# Schematics_Rev_2.net
KiCad netlist of a schematic drawn in EAGLE
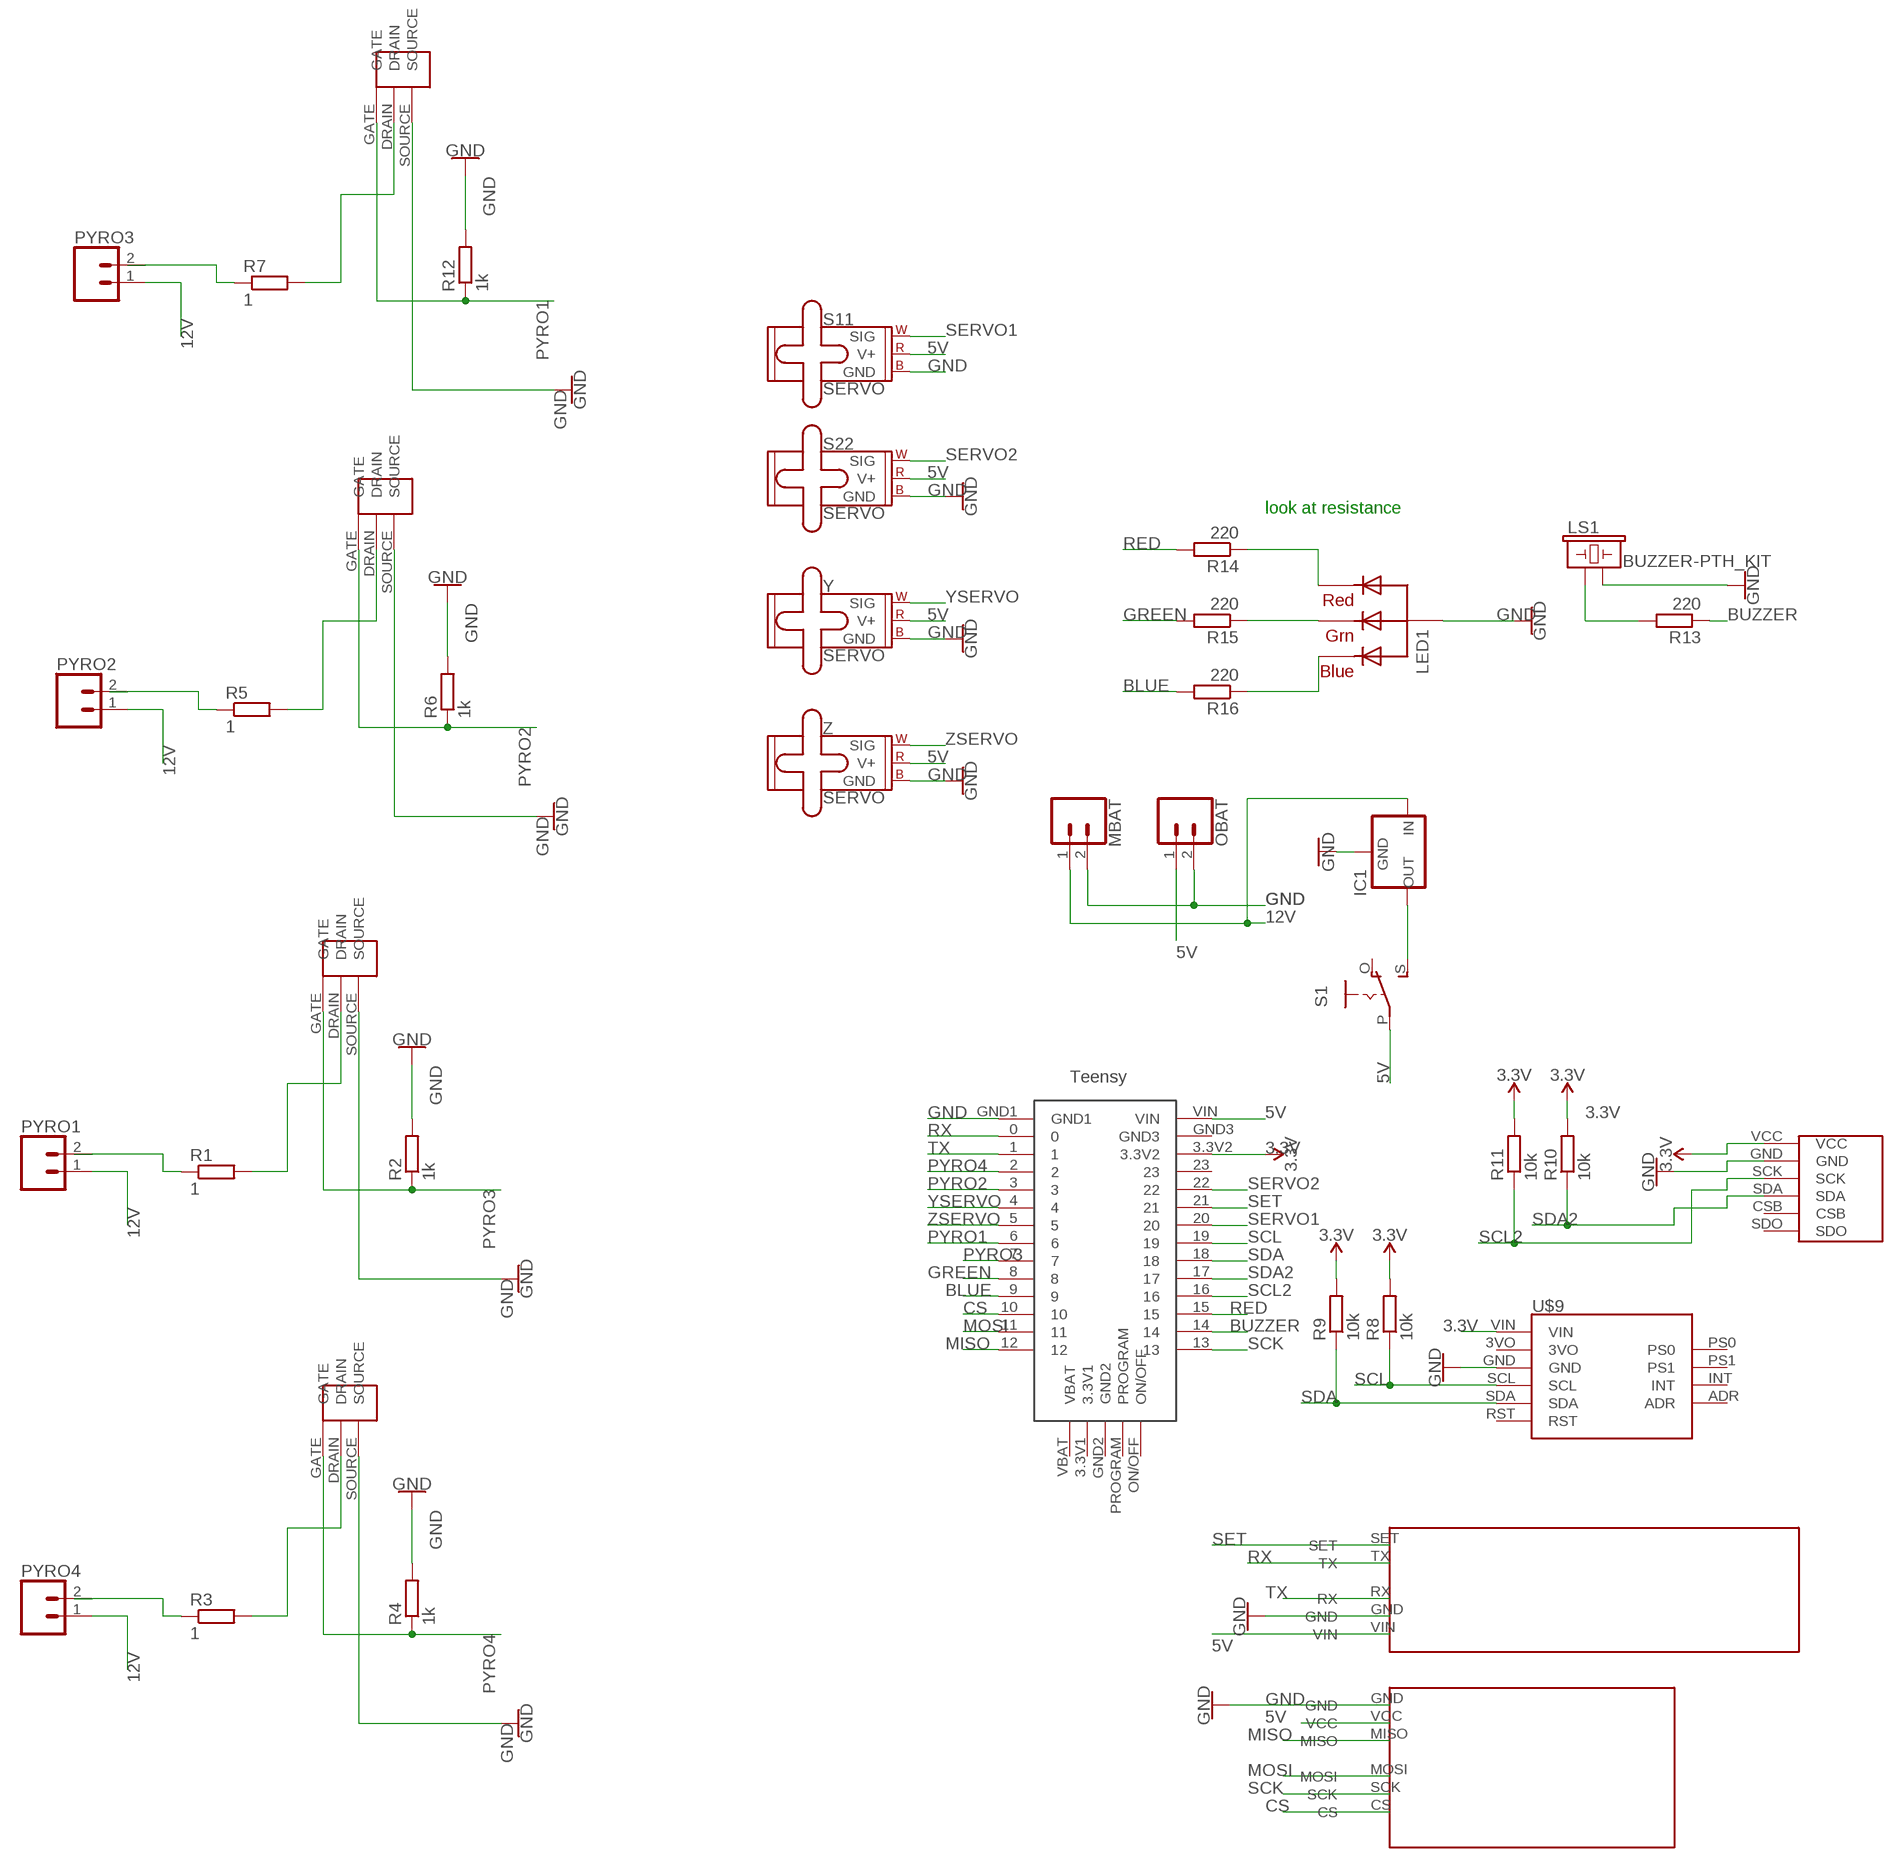
[diagram p0: schematic, sheet 1]

(export (version "E")
  (design (tool "Eeschema 10.0.6"))
  (components
    (comp (ref "IC1")
      (value "78XXS")
      (footprint "eagle-import:78XXS")
      (libsource (lib "eagle-import") (part "78XXS"))
    )
    (comp (ref "LED1")
      (value "RGBLED_CA-5MM")
      (footprint "eagle-import:LED5MMRGB")
      (libsource (lib "eagle-import") (part "RGBLED_CA-5MM"))
    )
    (comp (ref "LS1")
      (value "BUZZER-PTH_KIT")
      (footprint "eagle-import:BUZZER-12MM-KIT")
      (libsource (lib "eagle-import") (part "BUZZER-PTH_KIT"))
    )
    (comp (ref "MBAT")
      (value "CONN_023.5MM")
      (footprint "eagle-import:SCREWTERMINAL-3.5MM-2")
      (libsource (lib "eagle-import") (part "CONN_023.5MM"))
    )
    (comp (ref "OBAT")
      (value "CONN_023.5MM")
      (footprint "eagle-import:SCREWTERMINAL-3.5MM-2")
      (libsource (lib "eagle-import") (part "CONN_023.5MM"))
    )
    (comp (ref "PYRO1")
      (value "CONN_023.5MM")
      (footprint "eagle-import:SCREWTERMINAL-3.5MM-2")
      (libsource (lib "eagle-import") (part "CONN_023.5MM"))
    )
    (comp (ref "PYRO2")
      (value "CONN_023.5MM")
      (footprint "eagle-import:SCREWTERMINAL-3.5MM-2")
      (libsource (lib "eagle-import") (part "CONN_023.5MM"))
    )
    (comp (ref "PYRO3")
      (value "CONN_023.5MM")
      (footprint "eagle-import:SCREWTERMINAL-3.5MM-2")
      (libsource (lib "eagle-import") (part "CONN_023.5MM"))
    )
    (comp (ref "PYRO4")
      (value "CONN_023.5MM")
      (footprint "eagle-import:SCREWTERMINAL-3.5MM-2")
      (libsource (lib "eagle-import") (part "CONN_023.5MM"))
    )
    (comp (ref "R1")
      (value "1")
      (footprint "eagle-import:0204_7")
      (libsource (lib "eagle-import") (part "R-EU_0204/7"))
    )
    (comp (ref "R2")
      (value "1k")
      (footprint "eagle-import:0204_7")
      (libsource (lib "eagle-import") (part "R-EU_0204/7"))
    )
    (comp (ref "R3")
      (value "1")
      (footprint "eagle-import:0204_7")
      (libsource (lib "eagle-import") (part "R-EU_0204/7"))
    )
    (comp (ref "R4")
      (value "1k")
      (footprint "eagle-import:0204_7")
      (libsource (lib "eagle-import") (part "R-EU_0204/7"))
    )
    (comp (ref "R5")
      (value "1")
      (footprint "eagle-import:0204_7")
      (libsource (lib "eagle-import") (part "R-EU_0204/7"))
    )
    (comp (ref "R6")
      (value "1k")
      (footprint "eagle-import:0204_7")
      (libsource (lib "eagle-import") (part "R-EU_0204/7"))
    )
    (comp (ref "R7")
      (value "1")
      (footprint "eagle-import:0204_7")
      (libsource (lib "eagle-import") (part "R-EU_0204/7"))
    )
    (comp (ref "R8")
      (value "10k")
      (footprint "eagle-import:0204_7")
      (libsource (lib "eagle-import") (part "R-EU_0204/7"))
    )
    (comp (ref "R9")
      (value "10k")
      (footprint "eagle-import:0204_7")
      (libsource (lib "eagle-import") (part "R-EU_0204/7"))
    )
    (comp (ref "R10")
      (value "10k")
      (footprint "eagle-import:0204_7")
      (libsource (lib "eagle-import") (part "R-EU_0204/7"))
    )
    (comp (ref "R11")
      (value "10k")
      (footprint "eagle-import:0204_7")
      (libsource (lib "eagle-import") (part "R-EU_0204/7"))
    )
    (comp (ref "R12")
      (value "1k")
      (footprint "eagle-import:0204_7")
      (libsource (lib "eagle-import") (part "R-EU_0204/7"))
    )
    (comp (ref "R13")
      (value "220")
      (footprint "eagle-import:0204_7")
      (libsource (lib "eagle-import") (part "R-EU_0204/7"))
    )
    (comp (ref "R14")
      (value "220")
      (footprint "eagle-import:0204_7")
      (libsource (lib "eagle-import") (part "R-EU_0204/7"))
    )
    (comp (ref "R15")
      (value "220")
      (footprint "eagle-import:0204_7")
      (libsource (lib "eagle-import") (part "R-EU_0204/7"))
    )
    (comp (ref "R16")
      (value "220")
      (footprint "eagle-import:0204_7")
      (libsource (lib "eagle-import") (part "R-EU_0204/7"))
    )
    (comp (ref "S1")
      (value "EG1218S")
      (footprint "eagle-import:EG1218")
      (libsource (lib "eagle-import") (part "EG1218S"))
    )
    (comp (ref "S11")
      (value "SERVO")
      (footprint "eagle-import:1X03")
      (libsource (lib "eagle-import") (part "SERVO"))
    )
    (comp (ref "S22")
      (value "SERVO")
      (footprint "eagle-import:1X03")
      (libsource (lib "eagle-import") (part "SERVO"))
    )
    (comp (ref "U$1")
      (value "TEENSY-4.0")
      (footprint "eagle-import:TEENSY-4.0")
      (libsource (lib "eagle-import") (part "TEENSY-4.0"))
    )
    (comp (ref "U$2")
      (value "MICROSD")
      (footprint "eagle-import:MICROSD")
      (libsource (lib "eagle-import") (part "MICROSD"))
    )
    (comp (ref "U$3")
      (value "BMP280")
      (footprint "eagle-import:BMP280")
      (libsource (lib "eagle-import") (part "BMP280"))
    )
    (comp (ref "U$4")
      (value "HC-12")
      (footprint "eagle-import:HC-12")
      (libsource (lib "eagle-import") (part "HC-12"))
    )
    (comp (ref "U$5")
      (value "IRF520")
      (footprint "eagle-import:IRF520")
      (libsource (lib "eagle-import") (part "IRF520"))
    )
    (comp (ref "U$6")
      (value "IRF520")
      (footprint "eagle-import:IRF520")
      (libsource (lib "eagle-import") (part "IRF520"))
    )
    (comp (ref "U$7")
      (value "IRF520")
      (footprint "eagle-import:IRF520")
      (libsource (lib "eagle-import") (part "IRF520"))
    )
    (comp (ref "U$8")
      (value "IRF520")
      (footprint "eagle-import:IRF520")
      (libsource (lib "eagle-import") (part "IRF520"))
    )
    (comp (ref "U$9")
      (value "BNO-055")
      (footprint "eagle-import:BNO-055")
      (libsource (lib "eagle-import") (part "BNO-055"))
    )
    (comp (ref "Y")
      (value "SERVO")
      (footprint "eagle-import:1X03")
      (libsource (lib "eagle-import") (part "SERVO"))
    )
    (comp (ref "Z")
      (value "SERVO")
      (footprint "eagle-import:1X03")
      (libsource (lib "eagle-import") (part "SERVO"))
    )
  )
  (nets
    (net (code "1") (name "/5V") (class "Default")
      (node (ref "OBAT") (pin "1") (pinfunction "1_1") (pintype "passive"))
      (node (ref "S1") (pin "P") (pinfunction "P_P") (pintype "passive"))
      (node (ref "S11") (pin "2") (pinfunction "V+_2") (pintype "bidirectional"))
      (node (ref "S22") (pin "2") (pinfunction "V+_2") (pintype "bidirectional"))
      (node (ref "U$1") (pin "VIN") (pinfunction "VIN_VIN") (pintype "bidirectional"))
      (node (ref "U$2") (pin "VCC") (pinfunction "VCC_VCC") (pintype "bidirectional"))
      (node (ref "U$4") (pin "VIN") (pinfunction "VIN_VIN") (pintype "bidirectional"))
      (node (ref "Y") (pin "2") (pinfunction "V+_2") (pintype "bidirectional"))
      (node (ref "Z") (pin "2") (pinfunction "V+_2") (pintype "bidirectional"))
    )
    (net (code "2") (name "/12V") (class "Default")
      (node (ref "IC1") (pin "IN") (pinfunction "IN_IN") (pintype "input"))
      (node (ref "MBAT") (pin "1") (pinfunction "1_1") (pintype "passive"))
      (node (ref "PYRO1") (pin "1") (pinfunction "1_1") (pintype "passive"))
      (node (ref "PYRO2") (pin "1") (pinfunction "1_1") (pintype "passive"))
      (node (ref "PYRO3") (pin "1") (pinfunction "1_1") (pintype "passive"))
      (node (ref "PYRO4") (pin "1") (pinfunction "1_1") (pintype "passive"))
    )
    (net (code "3") (name "/BLUE") (class "Default")
      (node (ref "R16") (pin "2") (pinfunction "2_2") (pintype "passive"))
      (node (ref "U$1") (pin "9") (pinfunction "9_9") (pintype "bidirectional"))
    )
    (net (code "4") (name "/BUZZER") (class "Default")
      (node (ref "R13") (pin "1") (pinfunction "1_1") (pintype "passive"))
      (node (ref "U$1") (pin "14") (pinfunction "14_14") (pintype "bidirectional"))
    )
    (net (code "5") (name "/CS") (class "Default")
      (node (ref "U$1") (pin "10") (pinfunction "10_10") (pintype "bidirectional"))
      (node (ref "U$2") (pin "CS") (pinfunction "CS_CS") (pintype "bidirectional"))
    )
    (net (code "6") (name "/GREEN") (class "Default")
      (node (ref "R15") (pin "2") (pinfunction "2_2") (pintype "passive"))
      (node (ref "U$1") (pin "8") (pinfunction "8_8") (pintype "bidirectional"))
    )
    (net (code "7") (name "/MISO") (class "Default")
      (node (ref "U$1") (pin "12") (pinfunction "12_12") (pintype "bidirectional"))
      (node (ref "U$2") (pin "MISO") (pinfunction "MISO_MISO") (pintype "bidirectional"))
    )
    (net (code "8") (name "/MOSI") (class "Default")
      (node (ref "U$1") (pin "11") (pinfunction "11_11") (pintype "bidirectional"))
      (node (ref "U$2") (pin "MOSI") (pinfunction "MOSI_MOSI") (pintype "bidirectional"))
    )
    (net (code "9") (name "/PYRO1") (class "Default")
      (node (ref "R12") (pin "1") (pinfunction "1_1") (pintype "passive"))
      (node (ref "U$1") (pin "6") (pinfunction "6_6") (pintype "bidirectional"))
      (node (ref "U$8") (pin "GATE") (pinfunction "GATE_GATE") (pintype "bidirectional"))
    )
    (net (code "10") (name "/PYRO2") (class "Default")
      (node (ref "R6") (pin "1") (pinfunction "1_1") (pintype "passive"))
      (node (ref "U$1") (pin "3") (pinfunction "3_3") (pintype "bidirectional"))
      (node (ref "U$7") (pin "GATE") (pinfunction "GATE_GATE") (pintype "bidirectional"))
    )
    (net (code "11") (name "/PYRO3") (class "Default")
      (node (ref "R2") (pin "1") (pinfunction "1_1") (pintype "passive"))
      (node (ref "U$1") (pin "7") (pinfunction "7_7") (pintype "bidirectional"))
      (node (ref "U$6") (pin "GATE") (pinfunction "GATE_GATE") (pintype "bidirectional"))
    )
    (net (code "12") (name "/PYRO4") (class "Default")
      (node (ref "R4") (pin "1") (pinfunction "1_1") (pintype "passive"))
      (node (ref "U$1") (pin "2") (pinfunction "2_2") (pintype "bidirectional"))
      (node (ref "U$5") (pin "GATE") (pinfunction "GATE_GATE") (pintype "bidirectional"))
    )
    (net (code "13") (name "/RED") (class "Default")
      (node (ref "R14") (pin "2") (pinfunction "2_2") (pintype "passive"))
      (node (ref "U$1") (pin "15") (pinfunction "15_15") (pintype "bidirectional"))
    )
    (net (code "14") (name "/RX") (class "Default")
      (node (ref "U$1") (pin "0") (pinfunction "0_0") (pintype "bidirectional"))
      (node (ref "U$4") (pin "TX") (pinfunction "TX_TX") (pintype "bidirectional"))
    )
    (net (code "15") (name "/SCK") (class "Default")
      (node (ref "U$1") (pin "13") (pinfunction "13_13") (pintype "bidirectional"))
      (node (ref "U$2") (pin "SCK") (pinfunction "SCK_SCK") (pintype "bidirectional"))
    )
    (net (code "16") (name "/SCL") (class "Default")
      (node (ref "R8") (pin "1") (pinfunction "1_1") (pintype "passive"))
      (node (ref "U$1") (pin "19") (pinfunction "19_19") (pintype "bidirectional"))
      (node (ref "U$9") (pin "SCL") (pinfunction "SCL_SCL") (pintype "bidirectional"))
    )
    (net (code "17") (name "/SCL2") (class "Default")
      (node (ref "R11") (pin "1") (pinfunction "1_1") (pintype "passive"))
      (node (ref "U$1") (pin "16") (pinfunction "16_16") (pintype "bidirectional"))
      (node (ref "U$3") (pin "SCK") (pinfunction "SCK_SCK") (pintype "bidirectional"))
    )
    (net (code "18") (name "/SDA") (class "Default")
      (node (ref "R9") (pin "1") (pinfunction "1_1") (pintype "passive"))
      (node (ref "U$1") (pin "18") (pinfunction "18_18") (pintype "bidirectional"))
      (node (ref "U$9") (pin "SDA") (pinfunction "SDA_SDA") (pintype "bidirectional"))
    )
    (net (code "19") (name "/SDA2") (class "Default")
      (node (ref "R10") (pin "1") (pinfunction "1_1") (pintype "passive"))
      (node (ref "U$1") (pin "17") (pinfunction "17_17") (pintype "bidirectional"))
      (node (ref "U$3") (pin "SDA") (pinfunction "SDA_SDA") (pintype "bidirectional"))
    )
    (net (code "20") (name "/SERVO1") (class "Default")
      (node (ref "S11") (pin "1") (pinfunction "SIG_1") (pintype "bidirectional"))
      (node (ref "U$1") (pin "20") (pinfunction "20_20") (pintype "bidirectional"))
    )
    (net (code "21") (name "/SERVO2") (class "Default")
      (node (ref "S22") (pin "1") (pinfunction "SIG_1") (pintype "bidirectional"))
      (node (ref "U$1") (pin "22") (pinfunction "22_22") (pintype "bidirectional"))
    )
    (net (code "22") (name "/SET") (class "Default")
      (node (ref "U$1") (pin "21") (pinfunction "21_21") (pintype "bidirectional"))
      (node (ref "U$4") (pin "SET") (pinfunction "SET_SET") (pintype "bidirectional"))
    )
    (net (code "23") (name "/TX") (class "Default")
      (node (ref "U$1") (pin "1") (pinfunction "1_1") (pintype "bidirectional"))
      (node (ref "U$4") (pin "RX") (pinfunction "RX_RX") (pintype "bidirectional"))
    )
    (net (code "24") (name "/YSERVO") (class "Default")
      (node (ref "U$1") (pin "4") (pinfunction "4_4") (pintype "bidirectional"))
      (node (ref "Y") (pin "1") (pinfunction "SIG_1") (pintype "bidirectional"))
    )
    (net (code "25") (name "/ZSERVO") (class "Default")
      (node (ref "U$1") (pin "5") (pinfunction "5_5") (pintype "bidirectional"))
      (node (ref "Z") (pin "1") (pinfunction "SIG_1") (pintype "bidirectional"))
    )
    (net (code "26") (name "3.3V") (class "Default")
      (node (ref "R10") (pin "2") (pinfunction "2_2") (pintype "passive"))
      (node (ref "R11") (pin "2") (pinfunction "2_2") (pintype "passive"))
      (node (ref "R8") (pin "2") (pinfunction "2_2") (pintype "passive"))
      (node (ref "R9") (pin "2") (pinfunction "2_2") (pintype "passive"))
      (node (ref "U$1") (pin "3.3V2") (pinfunction "3.3V2_3.3V2") (pintype "bidirectional"))
      (node (ref "U$3") (pin "VCC") (pinfunction "VCC_VCC") (pintype "bidirectional"))
      (node (ref "U$9") (pin "VIN") (pinfunction "VIN_VIN") (pintype "bidirectional"))
    )
    (net (code "27") (name "GND") (class "Default")
      (node (ref "IC1") (pin "GND") (pinfunction "GND_GND") (pintype "input"))
      (node (ref "LED1") (pin "2") (pinfunction "VCC_2") (pintype "bidirectional"))
      (node (ref "LS1") (pin "-") (pinfunction "2_-") (pintype "passive"))
      (node (ref "MBAT") (pin "2") (pinfunction "2_2") (pintype "passive"))
      (node (ref "OBAT") (pin "2") (pinfunction "2_2") (pintype "passive"))
      (node (ref "R12") (pin "2") (pinfunction "2_2") (pintype "passive"))
      (node (ref "R2") (pin "2") (pinfunction "2_2") (pintype "passive"))
      (node (ref "R4") (pin "2") (pinfunction "2_2") (pintype "passive"))
      (node (ref "R6") (pin "2") (pinfunction "2_2") (pintype "passive"))
      (node (ref "S11") (pin "3") (pinfunction "GND_3") (pintype "bidirectional"))
      (node (ref "S22") (pin "3") (pinfunction "GND_3") (pintype "bidirectional"))
      (node (ref "U$1") (pin "GND1") (pinfunction "GND1_GND1") (pintype "bidirectional"))
      (node (ref "U$2") (pin "GND") (pinfunction "GND_GND") (pintype "bidirectional"))
      (node (ref "U$3") (pin "GND") (pinfunction "GND_GND") (pintype "bidirectional"))
      (node (ref "U$4") (pin "GND") (pinfunction "GND_GND") (pintype "bidirectional"))
      (node (ref "U$5") (pin "SOURCE") (pinfunction "SOURCE_SOURCE") (pintype "bidirectional"))
      (node (ref "U$6") (pin "SOURCE") (pinfunction "SOURCE_SOURCE") (pintype "bidirectional"))
      (node (ref "U$7") (pin "SOURCE") (pinfunction "SOURCE_SOURCE") (pintype "bidirectional"))
      (node (ref "U$8") (pin "SOURCE") (pinfunction "SOURCE_SOURCE") (pintype "bidirectional"))
      (node (ref "U$9") (pin "GND") (pinfunction "GND_GND") (pintype "bidirectional"))
      (node (ref "Y") (pin "3") (pinfunction "GND_3") (pintype "bidirectional"))
      (node (ref "Z") (pin "3") (pinfunction "GND_3") (pintype "bidirectional"))
    )
    (net (code "28") (name "Net-(IC1-PadOUT)") (class "Default")
      (node (ref "IC1") (pin "OUT") (pinfunction "OUT_OUT") (pintype "passive"))
      (node (ref "S1") (pin "S") (pinfunction "S_S") (pintype "passive"))
    )
    (net (code "29") (name "Net-(LED1-BLUE)") (class "Default")
      (node (ref "LED1") (pin "4") (pinfunction "BLUE_4") (pintype "bidirectional"))
      (node (ref "R16") (pin "1") (pinfunction "1_1") (pintype "passive"))
    )
    (net (code "30") (name "Net-(LED1-GREEN)") (class "Default")
      (node (ref "LED1") (pin "3") (pinfunction "GREEN_3") (pintype "bidirectional"))
      (node (ref "R15") (pin "1") (pinfunction "1_1") (pintype "passive"))
    )
    (net (code "31") (name "Net-(LED1-RED)") (class "Default")
      (node (ref "LED1") (pin "1") (pinfunction "RED_1") (pintype "bidirectional"))
      (node (ref "R14") (pin "1") (pinfunction "1_1") (pintype "passive"))
    )
    (net (code "32") (name "Net-(LS1-1)") (class "Default")
      (node (ref "LS1") (pin "+") (pinfunction "1_+") (pintype "passive"))
      (node (ref "R13") (pin "2") (pinfunction "2_2") (pintype "passive"))
    )
    (net (code "33") (name "Net-(PYRO1-Pad2)") (class "Default")
      (node (ref "PYRO1") (pin "2") (pinfunction "2_2") (pintype "passive"))
      (node (ref "R1") (pin "1") (pinfunction "1_1") (pintype "passive"))
    )
    (net (code "34") (name "Net-(PYRO2-Pad2)") (class "Default")
      (node (ref "PYRO2") (pin "2") (pinfunction "2_2") (pintype "passive"))
      (node (ref "R5") (pin "1") (pinfunction "1_1") (pintype "passive"))
    )
    (net (code "35") (name "Net-(PYRO3-Pad2)") (class "Default")
      (node (ref "PYRO3") (pin "2") (pinfunction "2_2") (pintype "passive"))
      (node (ref "R7") (pin "1") (pinfunction "1_1") (pintype "passive"))
    )
    (net (code "36") (name "Net-(PYRO4-Pad2)") (class "Default")
      (node (ref "PYRO4") (pin "2") (pinfunction "2_2") (pintype "passive"))
      (node (ref "R3") (pin "1") (pinfunction "1_1") (pintype "passive"))
    )
    (net (code "37") (name "Net-(R1-Pad2)") (class "Default")
      (node (ref "R1") (pin "2") (pinfunction "2_2") (pintype "passive"))
      (node (ref "U$6") (pin "DRAIN") (pinfunction "DRAIN_DRAIN") (pintype "bidirectional"))
    )
    (net (code "38") (name "Net-(R3-Pad2)") (class "Default")
      (node (ref "R3") (pin "2") (pinfunction "2_2") (pintype "passive"))
      (node (ref "U$5") (pin "DRAIN") (pinfunction "DRAIN_DRAIN") (pintype "bidirectional"))
    )
    (net (code "39") (name "Net-(R5-Pad2)") (class "Default")
      (node (ref "R5") (pin "2") (pinfunction "2_2") (pintype "passive"))
      (node (ref "U$7") (pin "DRAIN") (pinfunction "DRAIN_DRAIN") (pintype "bidirectional"))
    )
    (net (code "40") (name "Net-(R7-Pad2)") (class "Default")
      (node (ref "R7") (pin "2") (pinfunction "2_2") (pintype "passive"))
      (node (ref "U$8") (pin "DRAIN") (pinfunction "DRAIN_DRAIN") (pintype "bidirectional"))
    )
    (net (code "41") (name "unconnected-(S1-PadO)") (class "Default")
      (node (ref "S1") (pin "O") (pinfunction "O_O") (pintype "passive"))
    )
    (net (code "42") (name "unconnected-(U$1-Pad3.3V1)") (class "Default")
      (node (ref "U$1") (pin "3.3V1") (pinfunction "3.3V1_3.3V1") (pintype "bidirectional"))
    )
    (net (code "43") (name "unconnected-(U$1-Pad23)") (class "Default")
      (node (ref "U$1") (pin "23") (pinfunction "23_23") (pintype "bidirectional"))
    )
    (net (code "44") (name "unconnected-(U$1-PadGND2)") (class "Default")
      (node (ref "U$1") (pin "GND2") (pinfunction "GND2_GND2") (pintype "bidirectional"))
    )
    (net (code "45") (name "unconnected-(U$1-PadGND3)") (class "Default")
      (node (ref "U$1") (pin "GND3") (pinfunction "GND3_GND3") (pintype "bidirectional"))
    )
    (net (code "46") (name "unconnected-(U$1-PadON{slash}OFF)") (class "Default")
      (node (ref "U$1") (pin "ON/OFF") (pinfunction "ON/OFF_ON/OFF") (pintype "bidirectional"))
    )
    (net (code "47") (name "unconnected-(U$1-PadPROGRAM)") (class "Default")
      (node (ref "U$1") (pin "PROGRAM") (pinfunction "PROGRAM_PROGRAM") (pintype "bidirectional"))
    )
    (net (code "48") (name "unconnected-(U$1-PadVBAT)") (class "Default")
      (node (ref "U$1") (pin "VBAT") (pinfunction "VBAT_VBAT") (pintype "bidirectional"))
    )
    (net (code "49") (name "unconnected-(U$3-PadCSB)") (class "Default")
      (node (ref "U$3") (pin "CSB") (pinfunction "CSB_CSB") (pintype "bidirectional"))
    )
    (net (code "50") (name "unconnected-(U$3-PadSDO)") (class "Default")
      (node (ref "U$3") (pin "SDO") (pinfunction "SDO_SDO") (pintype "bidirectional"))
    )
    (net (code "51") (name "unconnected-(U$9-Pad3VO)") (class "Default")
      (node (ref "U$9") (pin "3VO") (pinfunction "3VO_3VO") (pintype "bidirectional"))
    )
    (net (code "52") (name "unconnected-(U$9-PadADR)") (class "Default")
      (node (ref "U$9") (pin "ADR") (pinfunction "ADR_ADR") (pintype "bidirectional"))
    )
    (net (code "53") (name "unconnected-(U$9-PadINT)") (class "Default")
      (node (ref "U$9") (pin "INT") (pinfunction "INT_INT") (pintype "bidirectional"))
    )
    (net (code "54") (name "unconnected-(U$9-PadPS0)") (class "Default")
      (node (ref "U$9") (pin "PS0") (pinfunction "PS0_PS0") (pintype "bidirectional"))
    )
    (net (code "55") (name "unconnected-(U$9-PadPS1)") (class "Default")
      (node (ref "U$9") (pin "PS1") (pinfunction "PS1_PS1") (pintype "bidirectional"))
    )
    (net (code "56") (name "unconnected-(U$9-PadRST)") (class "Default")
      (node (ref "U$9") (pin "RST") (pinfunction "RST_RST") (pintype "bidirectional"))
    )
  )
)
